# 5-gsm.net
KiCad netlist of a schematic drawn in Altium Designer
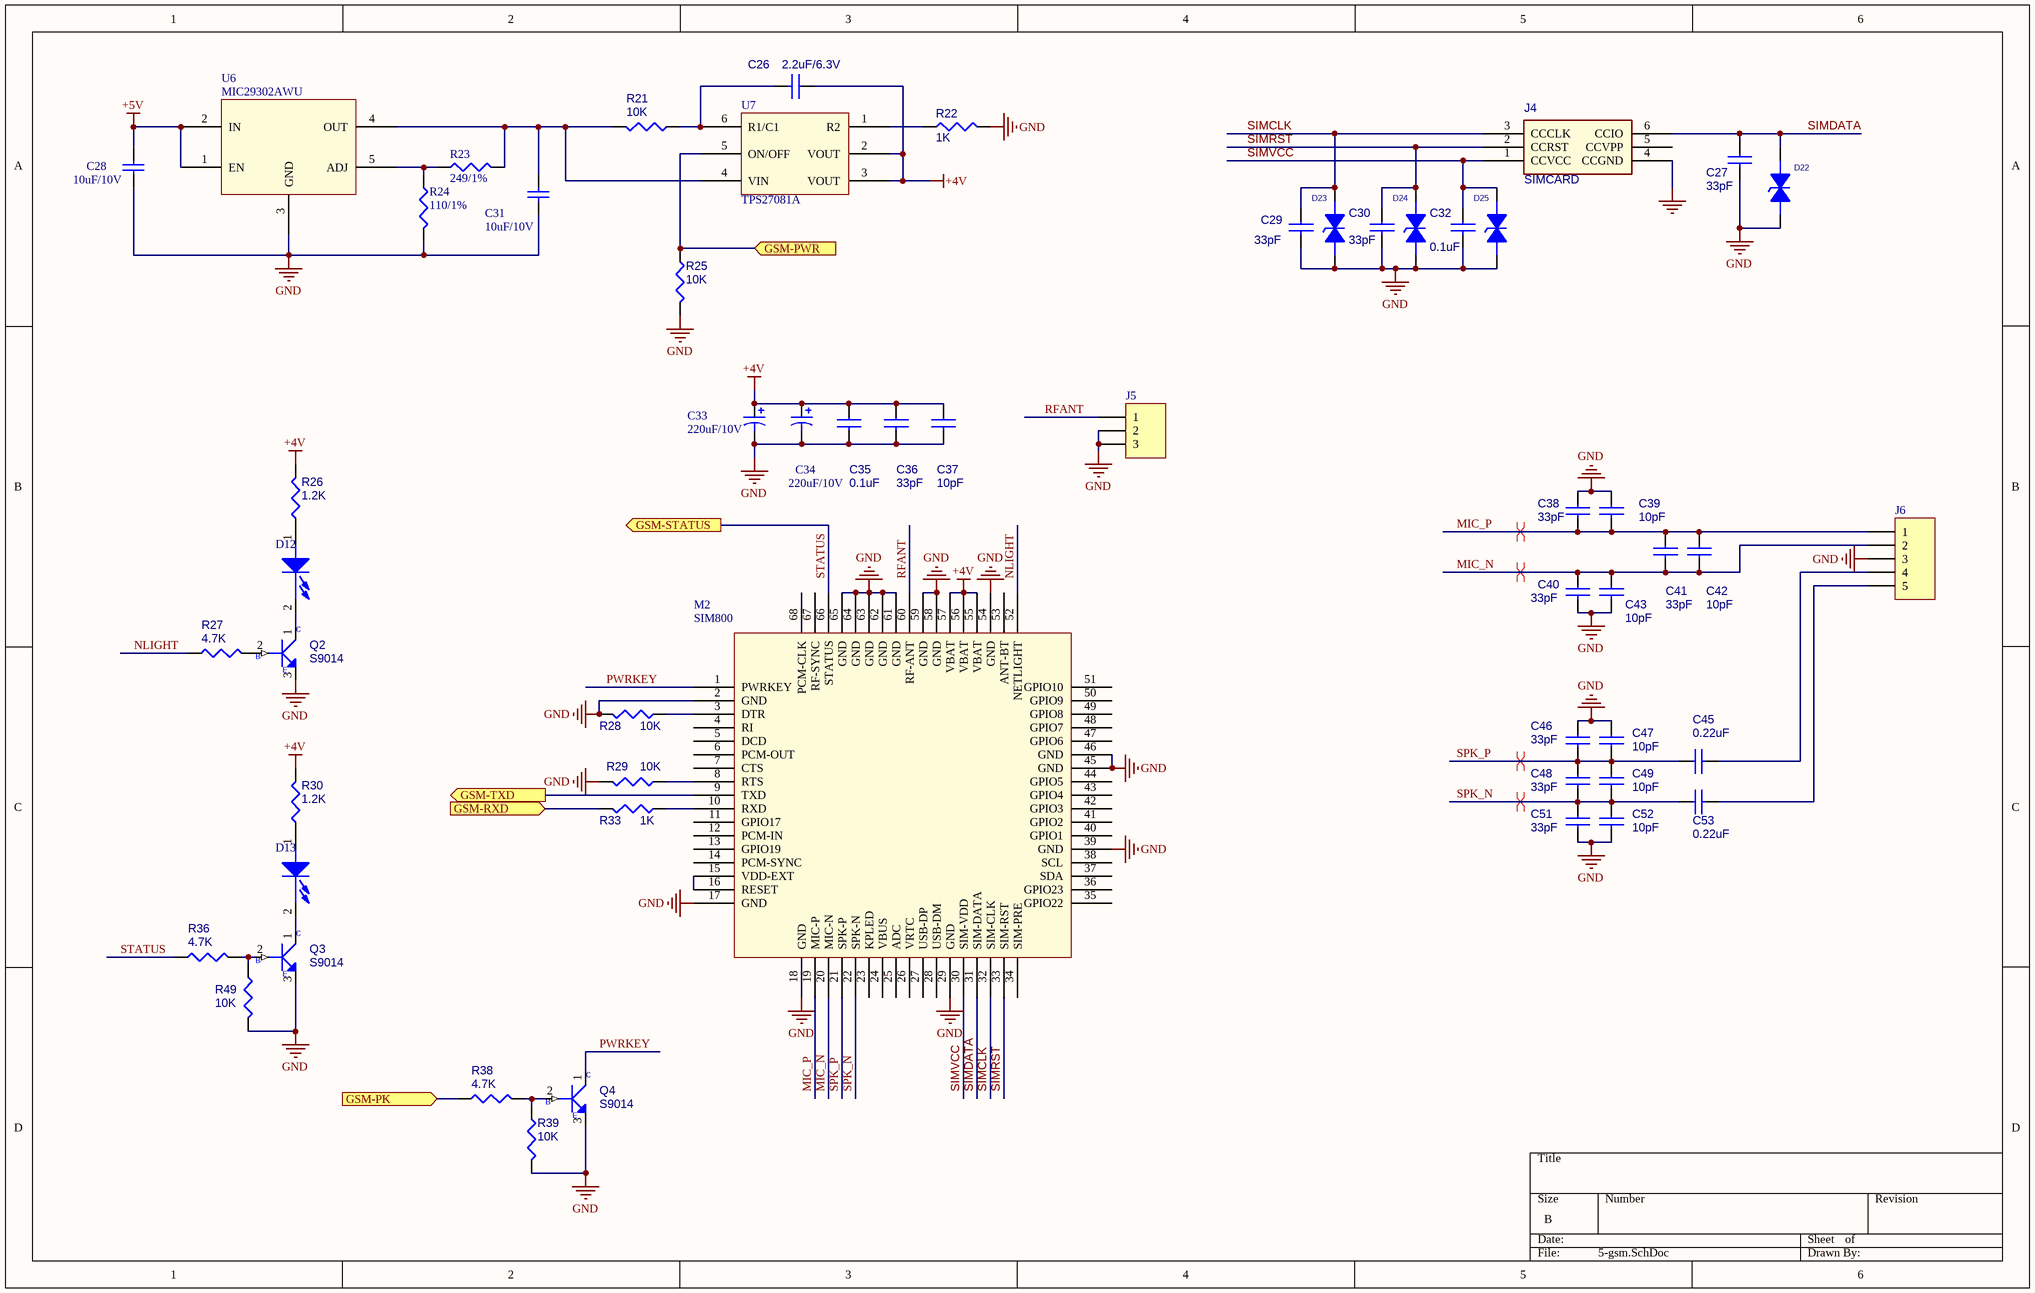
[diagram p0: 5-gsm.SchDoc]

(export (version "E")
  (design (tool "Eeschema 10.0.6"))
  (components
    (comp (ref "C26") (value "2.2uF/6.3V") (footprint "0603") (libsource (lib "*") (part "P_CAP NP")))
    (comp (ref "C27") (value "33pF") (libsource (lib "*") (part "P_CAP NP")))
    (comp (ref "C28")
      (value "10uF/10V")
      (footprint "1210")
      (description "Capacitor")
      (fields (field (name "PUBLISHER") "Altium Limited"))
      (libsource (lib "Miscellaneous Devices") (part "Cap"))
    )
    (comp (ref "C29") (value "33pF") (libsource (lib "*") (part "P_CAP NP")))
    (comp (ref "C30") (value "33pF") (libsource (lib "*") (part "P_CAP NP")))
    (comp (ref "C31")
      (value "10uF/10V")
      (footprint "1210")
      (description "Capacitor")
      (fields (field (name "PUBLISHER") "Altium Limited"))
      (libsource (lib "Miscellaneous Devices") (part "Cap"))
    )
    (comp (ref "C32") (value "0.1uF") (libsource (lib "*") (part "P_CAP NP")))
    (comp (ref "C33")
      (value "220uF/10V")
      (footprint "7343")
      (description "Polarized Capacitor (Radial)")
      (fields (field (name "PUBLISHER") "Altium Limited"))
      (libsource (lib "Miscellaneous Devices") (part "Cap Pol1"))
    )
    (comp (ref "C34")
      (value "220uF/10V")
      (footprint "7343")
      (description "Polarized Capacitor (Radial)")
      (fields (field (name "PUBLISHER") "Altium Limited"))
      (libsource (lib "Miscellaneous Devices") (part "Cap Pol1"))
    )
    (comp (ref "C35") (value "0.1uF") (libsource (lib "*") (part "P_CAP NP")))
    (comp (ref "C36") (value "33pF") (libsource (lib "*") (part "P_CAP NP")))
    (comp (ref "C37") (value "10pF") (libsource (lib "*") (part "P_CAP NP")))
    (comp (ref "C38") (value "33pF") (libsource (lib "*") (part "P_CAP NP")))
    (comp (ref "C39") (value "10pF") (libsource (lib "*") (part "P_CAP NP")))
    (comp (ref "C40") (value "33pF") (libsource (lib "*") (part "P_CAP NP")))
    (comp (ref "C41") (value "33pF") (libsource (lib "*") (part "P_CAP NP")))
    (comp (ref "C42") (value "10pF") (libsource (lib "*") (part "P_CAP NP")))
    (comp (ref "C43") (value "10pF") (libsource (lib "*") (part "P_CAP NP")))
    (comp (ref "C45") (value "0.22uF") (libsource (lib "*") (part "P_CAP NP")))
    (comp (ref "C46") (value "33pF") (libsource (lib "*") (part "P_CAP NP")))
    (comp (ref "C47") (value "10pF") (libsource (lib "*") (part "P_CAP NP")))
    (comp (ref "C48") (value "33pF") (libsource (lib "*") (part "P_CAP NP")))
    (comp (ref "C49") (value "10pF") (libsource (lib "*") (part "P_CAP NP")))
    (comp (ref "C51") (value "33pF") (libsource (lib "*") (part "P_CAP NP")))
    (comp (ref "C52") (value "10pF") (libsource (lib "*") (part "P_CAP NP")))
    (comp (ref "C53") (value "0.22uF") (libsource (lib "*") (part "P_CAP NP")))
    (comp (ref "D12") (value "LED GREEN") (footprint "LED0603") (libsource (lib "*") (part "LN01401_1")))
    (comp (ref "D13") (value "LED GREEN") (footprint "LED0603") (libsource (lib "*") (part "LN01401_1")))
    (comp (ref "D22") (value "SMV0402G5R6N121T") (footprint "0402") (libsource (lib "*") (part "PESD")))
    (comp (ref "D23") (value "SMV0402G5R6N121T") (footprint "0402") (libsource (lib "*") (part "PESD")))
    (comp (ref "D24") (value "SMV0402G5R6N121T") (footprint "0402") (libsource (lib "*") (part "PESD")))
    (comp (ref "D25") (value "SMV0402G5R6N121T") (footprint "0402") (libsource (lib "*") (part "PESD")))
    (comp (ref "J4") (value "SIMCARD") (footprint "SIM_CARD1") (libsource (lib "*") (part "SIMCARD")))
    (comp (ref "J5")
      (value "Header 3")
      (footprint "ANT")
      (description "Header, 3-Pin")
      (fields (field (name "PUBLISHER") "Altium Limited"))
      (libsource (lib "Miscellaneous Connectors") (part "Header 3"))
    )
    (comp (ref "J6")
      (value "Header 5")
      (footprint "CON-5PIN")
      (description "Header, 5-Pin")
      (fields (field (name "PUBLISHER") "Altium Limited"))
      (libsource (lib "Miscellaneous Connectors") (part "Header 5"))
    )
    (comp (ref "M2") (value "SIM800") (footprint "sim800") (libsource (lib "Schlib") (part "SIM800")))
    (comp (ref "Q2")
      (value "S9014")
      (footprint "NPN")
      (fields (field (name "PART NUMBER") "SB039040000"))
      (libsource (lib "*") (part "MMBT3904_NL_SOT23-3"))
    )
    (comp (ref "Q3")
      (value "S9014")
      (footprint "NPN")
      (fields (field (name "PART NUMBER") "SB039040000"))
      (libsource (lib "*") (part "MMBT3904_NL_SOT23-3"))
    )
    (comp (ref "Q4")
      (value "S9014")
      (footprint "NPN")
      (fields (field (name "PART NUMBER") "SB039040000"))
      (libsource (lib "*") (part "MMBT3904_NL_SOT23-3"))
    )
    (comp (ref "R21") (value "10K") (footprint "0603") (libsource (lib "*") (part "P_R")))
    (comp (ref "R22") (value "1K") (footprint "0603") (libsource (lib "*") (part "P_R")))
    (comp (ref "R23")
      (value "249/1%")
      (footprint "0603")
      (description "Resistor")
      (fields (field (name "PUBLISHER") "Altium Limited"))
      (libsource (lib "Miscellaneous Devices") (part "Res3"))
    )
    (comp (ref "R24")
      (value "110/1%")
      (footprint "0603")
      (description "Resistor")
      (fields (field (name "PUBLISHER") "Altium Limited"))
      (libsource (lib "Miscellaneous Devices") (part "Res3"))
    )
    (comp (ref "R25") (value "10K") (footprint "0603") (libsource (lib "*") (part "P_R")))
    (comp (ref "R26") (value "1.2K") (footprint "0603") (libsource (lib "*") (part "P_R")))
    (comp (ref "R27") (value "4.7K") (footprint "0603") (libsource (lib "*") (part "P_R")))
    (comp (ref "R28") (value "10K") (footprint "0603") (libsource (lib "*") (part "P_R")))
    (comp (ref "R29") (value "10K") (footprint "0603") (libsource (lib "*") (part "P_R")))
    (comp (ref "R30") (value "1.2K") (footprint "0603") (libsource (lib "*") (part "P_R")))
    (comp (ref "R33") (value "1K") (footprint "0603") (libsource (lib "*") (part "P_R")))
    (comp (ref "R36") (value "4.7K") (footprint "0603") (libsource (lib "*") (part "P_R")))
    (comp (ref "R38") (value "4.7K") (footprint "0603") (libsource (lib "*") (part "P_R")))
    (comp (ref "R39") (value "10K") (footprint "0603") (libsource (lib "*") (part "P_R")))
    (comp (ref "R49") (value "10K") (footprint "0603") (libsource (lib "*") (part "P_R")))
    (comp (ref "U6")
      (value "MIC29302AWU")
      (footprint "TO-263")
      (libsource (lib "Schlib") (part "MIC29302AWU"))
    )
    (comp (ref "U7") (value "TPS27081A") (footprint "SOT23-6") (libsource (lib "Schlib") (part "TPS27081A")))
  )
  (nets
    (net (code "1") (name "+4V") (class "Default")
      (node (ref "C26") (pin "1") (pinfunction "1_1") (pintype "passive"))
      (node (ref "C33") (pin "1") (pinfunction "1_1") (pintype "passive"))
      (node (ref "C34") (pin "1") (pinfunction "1_1") (pintype "passive"))
      (node (ref "C35") (pin "1") (pinfunction "1_1") (pintype "passive"))
      (node (ref "C36") (pin "1") (pinfunction "1_1") (pintype "passive"))
      (node (ref "C37") (pin "1") (pinfunction "1_1") (pintype "passive"))
      (node (ref "M2") (pin "55") (pinfunction "VBAT_55") (pintype "passive"))
      (node (ref "M2") (pin "56") (pinfunction "VBAT_56") (pintype "passive"))
      (node (ref "M2") (pin "57") (pinfunction "VBAT_57") (pintype "passive"))
      (node (ref "R26") (pin "1") (pinfunction "1_1") (pintype "passive"))
      (node (ref "R30") (pin "1") (pinfunction "1_1") (pintype "passive"))
      (node (ref "U7") (pin "2") (pinfunction "VOUT_2") (pintype "passive"))
      (node (ref "U7") (pin "3") (pinfunction "VOUT_3") (pintype "passive"))
    )
    (net (code "2") (name "+5V") (class "Default")
      (node (ref "C28") (pin "2") (pinfunction "2_2") (pintype "passive"))
      (node (ref "U6") (pin "1") (pinfunction "EN_1") (pintype "passive"))
      (node (ref "U6") (pin "2") (pinfunction "IN_2") (pintype "passive"))
    )
    (net (code "3") (name "/GSM-PK") (class "Default")
      (node (ref "R38") (pin "2") (pinfunction "2_2") (pintype "passive"))
    )
    (net (code "4") (name "/GSM-PWR") (class "Default")
      (node (ref "R25") (pin "2") (pinfunction "2_2") (pintype "passive"))
      (node (ref "U7") (pin "5") (pinfunction "ON/OFF_5") (pintype "passive"))
    )
    (net (code "5") (name "/GSM-RXD") (class "Default")
      (node (ref "R33") (pin "1") (pinfunction "1_1") (pintype "passive"))
    )
    (net (code "6") (name "/GSM-TXD") (class "Default")
      (node (ref "M2") (pin "9") (pinfunction "TXD_9") (pintype "passive"))
    )
    (net (code "7") (name "/MIC_N") (class "Default")
      (node (ref "C40") (pin "1") (pinfunction "1_1") (pintype "passive"))
      (node (ref "C41") (pin "2") (pinfunction "2_2") (pintype "passive"))
      (node (ref "C42") (pin "2") (pinfunction "2_2") (pintype "passive"))
      (node (ref "C43") (pin "1") (pinfunction "1_1") (pintype "passive"))
      (node (ref "J6") (pin "2") (pinfunction "2_2") (pintype "passive"))
      (node (ref "M2") (pin "20") (pinfunction "MIC-N_20") (pintype "passive"))
    )
    (net (code "8") (name "/MIC_P") (class "Default")
      (node (ref "C38") (pin "2") (pinfunction "2_2") (pintype "passive"))
      (node (ref "C39") (pin "2") (pinfunction "2_2") (pintype "passive"))
      (node (ref "C41") (pin "1") (pinfunction "1_1") (pintype "passive"))
      (node (ref "C42") (pin "1") (pinfunction "1_1") (pintype "passive"))
      (node (ref "J6") (pin "1") (pinfunction "1_1") (pintype "passive"))
      (node (ref "M2") (pin "19") (pinfunction "MIC-P_19") (pintype "passive"))
    )
    (net (code "9") (name "/NLIGHT") (class "Default")
      (node (ref "M2") (pin "52") (pinfunction "NETLIGHT_52") (pintype "passive"))
      (node (ref "R27") (pin "2") (pinfunction "2_2") (pintype "passive"))
    )
    (net (code "10") (name "/PWRKEY") (class "Default")
      (node (ref "M2") (pin "1") (pinfunction "PWRKEY_1") (pintype "passive"))
      (node (ref "Q4") (pin "1") (pinfunction "COLLECTOR_1") (pintype "passive"))
    )
    (net (code "11") (name "/RFANT") (class "Default")
      (node (ref "J5") (pin "1") (pinfunction "1_1") (pintype "passive"))
      (node (ref "M2") (pin "60") (pinfunction "RF-ANT_60") (pintype "passive"))
    )
    (net (code "12") (name "/SIMCLK") (class "Default")
      (node (ref "C29") (pin "1") (pinfunction "1_1") (pintype "passive"))
      (node (ref "D23") (pin "2") (pinfunction "2_2") (pintype "passive"))
      (node (ref "J4") (pin "3") (pinfunction "CCCLK_3") (pintype "passive"))
      (node (ref "M2") (pin "32") (pinfunction "SIM-CLK_32") (pintype "passive"))
    )
    (net (code "13") (name "/SIMDATA") (class "Default")
      (node (ref "C27") (pin "1") (pinfunction "1_1") (pintype "passive"))
      (node (ref "D22") (pin "2") (pinfunction "2_2") (pintype "passive"))
      (node (ref "J4") (pin "6") (pinfunction "CCIO_6") (pintype "passive"))
      (node (ref "M2") (pin "31") (pinfunction "SIM-DATA_31") (pintype "passive"))
    )
    (net (code "14") (name "/SIMRST") (class "Default")
      (node (ref "C30") (pin "1") (pinfunction "1_1") (pintype "passive"))
      (node (ref "D24") (pin "2") (pinfunction "2_2") (pintype "passive"))
      (node (ref "J4") (pin "2") (pinfunction "CCRST_2") (pintype "passive"))
      (node (ref "M2") (pin "33") (pinfunction "SIM-RST_33") (pintype "passive"))
    )
    (net (code "15") (name "/SIMVCC") (class "Default")
      (node (ref "C32") (pin "1") (pinfunction "1_1") (pintype "passive"))
      (node (ref "D25") (pin "2") (pinfunction "2_2") (pintype "passive"))
      (node (ref "J4") (pin "1") (pinfunction "CCVCC_1") (pintype "passive"))
      (node (ref "M2") (pin "30") (pinfunction "SIM-VDD_30") (pintype "passive"))
    )
    (net (code "16") (name "/SPK_N") (class "Default")
      (node (ref "C48") (pin "2") (pinfunction "2_2") (pintype "passive"))
      (node (ref "C49") (pin "2") (pinfunction "2_2") (pintype "passive"))
      (node (ref "C51") (pin "1") (pinfunction "1_1") (pintype "passive"))
      (node (ref "C52") (pin "1") (pinfunction "1_1") (pintype "passive"))
      (node (ref "C53") (pin "1") (pinfunction "1_1") (pintype "passive"))
      (node (ref "M2") (pin "22") (pinfunction "SPK-N_22") (pintype "passive"))
    )
    (net (code "17") (name "/SPK_P") (class "Default")
      (node (ref "C45") (pin "1") (pinfunction "1_1") (pintype "passive"))
      (node (ref "C46") (pin "2") (pinfunction "2_2") (pintype "passive"))
      (node (ref "C47") (pin "2") (pinfunction "2_2") (pintype "passive"))
      (node (ref "C48") (pin "1") (pinfunction "1_1") (pintype "passive"))
      (node (ref "C49") (pin "1") (pinfunction "1_1") (pintype "passive"))
      (node (ref "M2") (pin "21") (pinfunction "SPK-P_21") (pintype "passive"))
    )
    (net (code "18") (name "/STATUS") (class "Default")
      (node (ref "M2") (pin "66") (pinfunction "STATUS_66") (pintype "passive"))
      (node (ref "R36") (pin "2") (pinfunction "2_2") (pintype "passive"))
    )
    (net (code "19") (name "GND") (class "Default")
      (node (ref "C27") (pin "2") (pinfunction "2_2") (pintype "passive"))
      (node (ref "C28") (pin "1") (pinfunction "1_1") (pintype "passive"))
      (node (ref "C29") (pin "2") (pinfunction "2_2") (pintype "passive"))
      (node (ref "C30") (pin "2") (pinfunction "2_2") (pintype "passive"))
      (node (ref "C31") (pin "1") (pinfunction "1_1") (pintype "passive"))
      (node (ref "C32") (pin "2") (pinfunction "2_2") (pintype "passive"))
      (node (ref "C33") (pin "2") (pinfunction "2_2") (pintype "passive"))
      (node (ref "C34") (pin "2") (pinfunction "2_2") (pintype "passive"))
      (node (ref "C35") (pin "2") (pinfunction "2_2") (pintype "passive"))
      (node (ref "C36") (pin "2") (pinfunction "2_2") (pintype "passive"))
      (node (ref "C37") (pin "2") (pinfunction "2_2") (pintype "passive"))
      (node (ref "C38") (pin "1") (pinfunction "1_1") (pintype "passive"))
      (node (ref "C39") (pin "1") (pinfunction "1_1") (pintype "passive"))
      (node (ref "C40") (pin "2") (pinfunction "2_2") (pintype "passive"))
      (node (ref "C43") (pin "2") (pinfunction "2_2") (pintype "passive"))
      (node (ref "C46") (pin "1") (pinfunction "1_1") (pintype "passive"))
      (node (ref "C47") (pin "1") (pinfunction "1_1") (pintype "passive"))
      (node (ref "C51") (pin "2") (pinfunction "2_2") (pintype "passive"))
      (node (ref "C52") (pin "2") (pinfunction "2_2") (pintype "passive"))
      (node (ref "D22") (pin "1") (pinfunction "1_1") (pintype "passive"))
      (node (ref "D23") (pin "1") (pinfunction "1_1") (pintype "passive"))
      (node (ref "D24") (pin "1") (pinfunction "1_1") (pintype "passive"))
      (node (ref "D25") (pin "1") (pinfunction "1_1") (pintype "passive"))
      (node (ref "J4") (pin "4") (pinfunction "CCGND_4") (pintype "passive"))
      (node (ref "J5") (pin "2") (pinfunction "2_2") (pintype "passive"))
      (node (ref "J5") (pin "3") (pinfunction "3_3") (pintype "passive"))
      (node (ref "J6") (pin "3") (pinfunction "3_3") (pintype "passive"))
      (node (ref "M2") (pin "17") (pinfunction "GND_17") (pintype "passive"))
      (node (ref "M2") (pin "18") (pinfunction "GND_18") (pintype "passive"))
      (node (ref "M2") (pin "2") (pinfunction "GND_2") (pintype "passive"))
      (node (ref "M2") (pin "29") (pinfunction "GND_29") (pintype "passive"))
      (node (ref "M2") (pin "39") (pinfunction "GND_39") (pintype "passive"))
      (node (ref "M2") (pin "45") (pinfunction "GND_45") (pintype "passive"))
      (node (ref "M2") (pin "46") (pinfunction "GND_46") (pintype "passive"))
      (node (ref "M2") (pin "54") (pinfunction "GND_54") (pintype "passive"))
      (node (ref "M2") (pin "58") (pinfunction "GND_58") (pintype "passive"))
      (node (ref "M2") (pin "59") (pinfunction "GND_59") (pintype "passive"))
      (node (ref "M2") (pin "61") (pinfunction "GND_61") (pintype "passive"))
      (node (ref "M2") (pin "62") (pinfunction "GND_62") (pintype "passive"))
      (node (ref "M2") (pin "63") (pinfunction "GND_63") (pintype "passive"))
      (node (ref "M2") (pin "64") (pinfunction "GND_64") (pintype "passive"))
      (node (ref "M2") (pin "65") (pinfunction "GND_65") (pintype "passive"))
      (node (ref "Q2") (pin "3") (pinfunction "EMITTER_3") (pintype "passive"))
      (node (ref "Q3") (pin "3") (pinfunction "EMITTER_3") (pintype "passive"))
      (node (ref "Q4") (pin "3") (pinfunction "EMITTER_3") (pintype "passive"))
      (node (ref "R22") (pin "1") (pinfunction "1_1") (pintype "passive"))
      (node (ref "R24") (pin "2") (pinfunction "2_2") (pintype "passive"))
      (node (ref "R25") (pin "1") (pinfunction "1_1") (pintype "passive"))
      (node (ref "R28") (pin "1") (pinfunction "1_1") (pintype "passive"))
      (node (ref "R29") (pin "1") (pinfunction "1_1") (pintype "passive"))
      (node (ref "R39") (pin "1") (pinfunction "1_1") (pintype "passive"))
      (node (ref "R49") (pin "1") (pinfunction "1_1") (pintype "passive"))
      (node (ref "U6") (pin "3") (pinfunction "GND_3") (pintype "passive"))
    )
    (net (code "20") (name "Net-(C45-Pad2)") (class "Default")
      (node (ref "C45") (pin "2") (pinfunction "2_2") (pintype "passive"))
      (node (ref "J6") (pin "4") (pinfunction "4_4") (pintype "passive"))
    )
    (net (code "21") (name "Net-(C53-Pad2)") (class "Default")
      (node (ref "C53") (pin "2") (pinfunction "2_2") (pintype "passive"))
      (node (ref "J6") (pin "5") (pinfunction "5_5") (pintype "passive"))
    )
    (net (code "22") (name "Net-(D12-ANODE)") (class "Default")
      (node (ref "D12") (pin "1") (pinfunction "ANODE_1") (pintype "passive"))
      (node (ref "R26") (pin "2") (pinfunction "2_2") (pintype "passive"))
    )
    (net (code "23") (name "Net-(D12-CATHODE)") (class "Default")
      (node (ref "D12") (pin "2") (pinfunction "CATHODE_2") (pintype "passive"))
      (node (ref "Q2") (pin "1") (pinfunction "COLLECTOR_1") (pintype "passive"))
    )
    (net (code "24") (name "Net-(D13-ANODE)") (class "Default")
      (node (ref "D13") (pin "1") (pinfunction "ANODE_1") (pintype "passive"))
      (node (ref "R30") (pin "2") (pinfunction "2_2") (pintype "passive"))
    )
    (net (code "25") (name "Net-(D13-CATHODE)") (class "Default")
      (node (ref "D13") (pin "2") (pinfunction "CATHODE_2") (pintype "passive"))
      (node (ref "Q3") (pin "1") (pinfunction "COLLECTOR_1") (pintype "passive"))
    )
    (net (code "26") (name "Net-(M2-DTR)") (class "Default")
      (node (ref "M2") (pin "3") (pinfunction "DTR_3") (pintype "passive"))
      (node (ref "R28") (pin "2") (pinfunction "2_2") (pintype "passive"))
    )
    (net (code "27") (name "Net-(M2-RESET)") (class "Default")
      (node (ref "M2") (pin "15") (pinfunction "VDD-EXT_15") (pintype "passive"))
      (node (ref "M2") (pin "16") (pinfunction "RESET_16") (pintype "passive"))
    )
    (net (code "28") (name "Net-(M2-RTS)") (class "Default")
      (node (ref "M2") (pin "8") (pinfunction "RTS_8") (pintype "passive"))
      (node (ref "R29") (pin "2") (pinfunction "2_2") (pintype "passive"))
    )
    (net (code "29") (name "Net-(M2-RXD)") (class "Default")
      (node (ref "M2") (pin "10") (pinfunction "RXD_10") (pintype "passive"))
      (node (ref "R33") (pin "2") (pinfunction "2_2") (pintype "passive"))
    )
    (net (code "30") (name "Net-(Q2-BASE)") (class "Default")
      (node (ref "Q2") (pin "2") (pinfunction "BASE_2") (pintype "input"))
      (node (ref "R27") (pin "1") (pinfunction "1_1") (pintype "passive"))
    )
    (net (code "31") (name "Net-(Q3-BASE)") (class "Default")
      (node (ref "Q3") (pin "2") (pinfunction "BASE_2") (pintype "input"))
      (node (ref "R36") (pin "1") (pinfunction "1_1") (pintype "passive"))
      (node (ref "R49") (pin "2") (pinfunction "2_2") (pintype "passive"))
    )
    (net (code "32") (name "Net-(Q4-BASE)") (class "Default")
      (node (ref "Q4") (pin "2") (pinfunction "BASE_2") (pintype "input"))
      (node (ref "R38") (pin "1") (pinfunction "1_1") (pintype "passive"))
      (node (ref "R39") (pin "2") (pinfunction "2_2") (pintype "passive"))
    )
    (net (code "33") (name "Net-(U6-ADJ)") (class "Default")
      (node (ref "R23") (pin "1") (pinfunction "1_1") (pintype "passive"))
      (node (ref "R24") (pin "1") (pinfunction "1_1") (pintype "passive"))
      (node (ref "U6") (pin "5") (pinfunction "ADJ_5") (pintype "passive"))
    )
    (net (code "34") (name "Net-(U6-OUT)") (class "Default")
      (node (ref "C31") (pin "2") (pinfunction "2_2") (pintype "passive"))
      (node (ref "R21") (pin "1") (pinfunction "1_1") (pintype "passive"))
      (node (ref "R23") (pin "2") (pinfunction "2_2") (pintype "passive"))
      (node (ref "U6") (pin "4") (pinfunction "OUT_4") (pintype "passive"))
      (node (ref "U7") (pin "4") (pinfunction "VIN_4") (pintype "passive"))
    )
    (net (code "35") (name "Net-(U7-R1{slash}C1)") (class "Default")
      (node (ref "C26") (pin "2") (pinfunction "2_2") (pintype "passive"))
      (node (ref "R21") (pin "2") (pinfunction "2_2") (pintype "passive"))
      (node (ref "U7") (pin "6") (pinfunction "R1/C1_6") (pintype "passive"))
    )
    (net (code "36") (name "Net-(U7-R2)") (class "Default")
      (node (ref "R22") (pin "2") (pinfunction "2_2") (pintype "passive"))
      (node (ref "U7") (pin "1") (pinfunction "R2_1") (pintype "passive"))
    )
    (net (code "37") (name "unconnected-(J4-CCVPP-Pad5)") (class "Default")
      (node (ref "J4") (pin "5") (pinfunction "CCVPP_5") (pintype "passive"))
    )
    (net (code "38") (name "unconnected-(M2-ADC-Pad25)") (class "Default")
      (node (ref "M2") (pin "25") (pinfunction "ADC_25") (pintype "passive"))
    )
    (net (code "39") (name "unconnected-(M2-ANT-BT-Pad53)") (class "Default")
      (node (ref "M2") (pin "53") (pinfunction "ANT-BT_53") (pintype "passive"))
    )
    (net (code "40") (name "unconnected-(M2-CTS-Pad7)") (class "Default")
      (node (ref "M2") (pin "7") (pinfunction "CTS_7") (pintype "passive"))
    )
    (net (code "41") (name "unconnected-(M2-DCD-Pad5)") (class "Default")
      (node (ref "M2") (pin "5") (pinfunction "DCD_5") (pintype "passive"))
    )
    (net (code "42") (name "unconnected-(M2-GPIO1-Pad40)") (class "Default")
      (node (ref "M2") (pin "40") (pinfunction "GPIO1_40") (pintype "passive"))
    )
    (net (code "43") (name "unconnected-(M2-GPIO2-Pad41)") (class "Default")
      (node (ref "M2") (pin "41") (pinfunction "GPIO2_41") (pintype "passive"))
    )
    (net (code "44") (name "unconnected-(M2-GPIO3-Pad42)") (class "Default")
      (node (ref "M2") (pin "42") (pinfunction "GPIO3_42") (pintype "passive"))
    )
    (net (code "45") (name "unconnected-(M2-GPIO4-Pad43)") (class "Default")
      (node (ref "M2") (pin "43") (pinfunction "GPIO4_43") (pintype "passive"))
    )
    (net (code "46") (name "unconnected-(M2-GPIO5-Pad44)") (class "Default")
      (node (ref "M2") (pin "44") (pinfunction "GPIO5_44") (pintype "passive"))
    )
    (net (code "47") (name "unconnected-(M2-GPIO6-Pad47)") (class "Default")
      (node (ref "M2") (pin "47") (pinfunction "GPIO6_47") (pintype "passive"))
    )
    (net (code "48") (name "unconnected-(M2-GPIO7-Pad48)") (class "Default")
      (node (ref "M2") (pin "48") (pinfunction "GPIO7_48") (pintype "passive"))
    )
    (net (code "49") (name "unconnected-(M2-GPIO8-Pad49)") (class "Default")
      (node (ref "M2") (pin "49") (pinfunction "GPIO8_49") (pintype "passive"))
    )
    (net (code "50") (name "unconnected-(M2-GPIO9-Pad50)") (class "Default")
      (node (ref "M2") (pin "50") (pinfunction "GPIO9_50") (pintype "passive"))
    )
    (net (code "51") (name "unconnected-(M2-GPIO10-Pad51)") (class "Default")
      (node (ref "M2") (pin "51") (pinfunction "GPIO10_51") (pintype "passive"))
    )
    (net (code "52") (name "unconnected-(M2-GPIO17-Pad11)") (class "Default")
      (node (ref "M2") (pin "11") (pinfunction "GPIO17_11") (pintype "passive"))
    )
    (net (code "53") (name "unconnected-(M2-GPIO19-Pad13)") (class "Default")
      (node (ref "M2") (pin "13") (pinfunction "GPIO19_13") (pintype "passive"))
    )
    (net (code "54") (name "unconnected-(M2-GPIO22-Pad35)") (class "Default")
      (node (ref "M2") (pin "35") (pinfunction "GPIO22_35") (pintype "passive"))
    )
    (net (code "55") (name "unconnected-(M2-GPIO23-Pad36)") (class "Default")
      (node (ref "M2") (pin "36") (pinfunction "GPIO23_36") (pintype "passive"))
    )
    (net (code "56") (name "unconnected-(M2-KPLED-Pad23)") (class "Default")
      (node (ref "M2") (pin "23") (pinfunction "KPLED_23") (pintype "passive"))
    )
    (net (code "57") (name "unconnected-(M2-PCM-CLK-Pad68)") (class "Default")
      (node (ref "M2") (pin "68") (pinfunction "PCM-CLK_68") (pintype "passive"))
    )
    (net (code "58") (name "unconnected-(M2-PCM-IN-Pad12)") (class "Default")
      (node (ref "M2") (pin "12") (pinfunction "PCM-IN_12") (pintype "passive"))
    )
    (net (code "59") (name "unconnected-(M2-PCM-OUT-Pad6)") (class "Default")
      (node (ref "M2") (pin "6") (pinfunction "PCM-OUT_6") (pintype "passive"))
    )
    (net (code "60") (name "unconnected-(M2-PCM-SYNC-Pad14)") (class "Default")
      (node (ref "M2") (pin "14") (pinfunction "PCM-SYNC_14") (pintype "passive"))
    )
    (net (code "61") (name "unconnected-(M2-RF-SYNC-Pad67)") (class "Default")
      (node (ref "M2") (pin "67") (pinfunction "RF-SYNC_67") (pintype "passive"))
    )
    (net (code "62") (name "unconnected-(M2-RI-Pad4)") (class "Default")
      (node (ref "M2") (pin "4") (pinfunction "RI_4") (pintype "passive"))
    )
    (net (code "63") (name "unconnected-(M2-SCL-Pad38)") (class "Default")
      (node (ref "M2") (pin "38") (pinfunction "SCL_38") (pintype "passive"))
    )
    (net (code "64") (name "unconnected-(M2-SDA-Pad37)") (class "Default")
      (node (ref "M2") (pin "37") (pinfunction "SDA_37") (pintype "passive"))
    )
    (net (code "65") (name "unconnected-(M2-SIM-PRE-Pad34)") (class "Default")
      (node (ref "M2") (pin "34") (pinfunction "SIM-PRE_34") (pintype "passive"))
    )
    (net (code "66") (name "unconnected-(M2-USB-DM-Pad28)") (class "Default")
      (node (ref "M2") (pin "28") (pinfunction "USB-DM_28") (pintype "passive"))
    )
    (net (code "67") (name "unconnected-(M2-USB-DP-Pad27)") (class "Default")
      (node (ref "M2") (pin "27") (pinfunction "USB-DP_27") (pintype "passive"))
    )
    (net (code "68") (name "unconnected-(M2-VBUS-Pad24)") (class "Default")
      (node (ref "M2") (pin "24") (pinfunction "VBUS_24") (pintype "passive"))
    )
    (net (code "69") (name "unconnected-(M2-VRTC-Pad26)") (class "Default")
      (node (ref "M2") (pin "26") (pinfunction "VRTC_26") (pintype "passive"))
    )
  )
)
